# 2_Power.net
KiCad netlist of a schematic drawn in Altium Designer
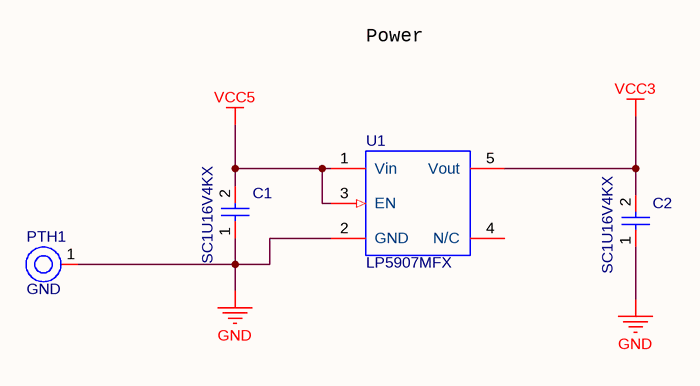
[diagram p0: 2_Power.SchDoc]

(export (version "E")
  (design (tool "Eeschema 10.0.6"))
  (components
    (comp (ref "C1")
      (value "SC1U16V4KX")
      (footprint "CAPC0805(2012)145_L")
      (description "CAP 1uF 16V ±10% 0805(1610 Metric) Thickness 0.6mm SMD")
      (libsource (lib "PUMAlib") (part "CAP(0805)1UF16V"))
    )
    (comp (ref "C2")
      (value "SC1U16V4KX")
      (footprint "CAPC0805(2012)145_L")
      (description "CAP 1uF 16V ±10% 0805(1610 Metric) Thickness 0.6mm SMD")
      (libsource (lib "PUMAlib") (part "CAP(0805)1UF16V"))
    )
    (comp (ref "PTH1")
      (value "GND")
      (footprint "POWERHOLE-LP")
      (description "1.2mm hole 2mm pad")
      (libsource (lib "PUMAlib") (part "PTH-1D2M"))
    )
    (comp (ref "U1")
      (value "LP5907MFX")
      (footprint "SOT95P280X145-5L")
      (description "3.3V 250mA")
      (libsource (lib "PUMAlib") (part "LP5907V3.3"))
    )
  )
  (nets
    (net (code "1") (name "GND") (class "Default")
      (node (ref "C1") (pin "1") (pinfunction "1_1") (pintype "passive"))
      (node (ref "C2") (pin "1") (pinfunction "1_1") (pintype "passive"))
      (node (ref "PTH1") (pin "1") (pinfunction "H1_1") (pintype "passive"))
      (node (ref "U1") (pin "2") (pinfunction "GND_2") (pintype "power_in"))
    )
    (net (code "2") (name "VCC3") (class "Default")
      (node (ref "C2") (pin "2") (pinfunction "2_2") (pintype "passive"))
      (node (ref "U1") (pin "5") (pinfunction "Vout_5") (pintype "power_in"))
    )
    (net (code "3") (name "VCC5") (class "Default")
      (node (ref "C1") (pin "2") (pinfunction "2_2") (pintype "passive"))
      (node (ref "U1") (pin "1") (pinfunction "Vin_1") (pintype "power_in"))
      (node (ref "U1") (pin "3") (pinfunction "EN_3") (pintype "input"))
    )
    (net (code "4") (name "unconnected-(U1-N{slash}C-Pad4)") (class "Default")
      (node (ref "U1") (pin "4") (pinfunction "N/C_4") (pintype "passive"))
    )
  )
)
